# RobotBooster.net
KiCad netlist of a schematic drawn in EAGLE
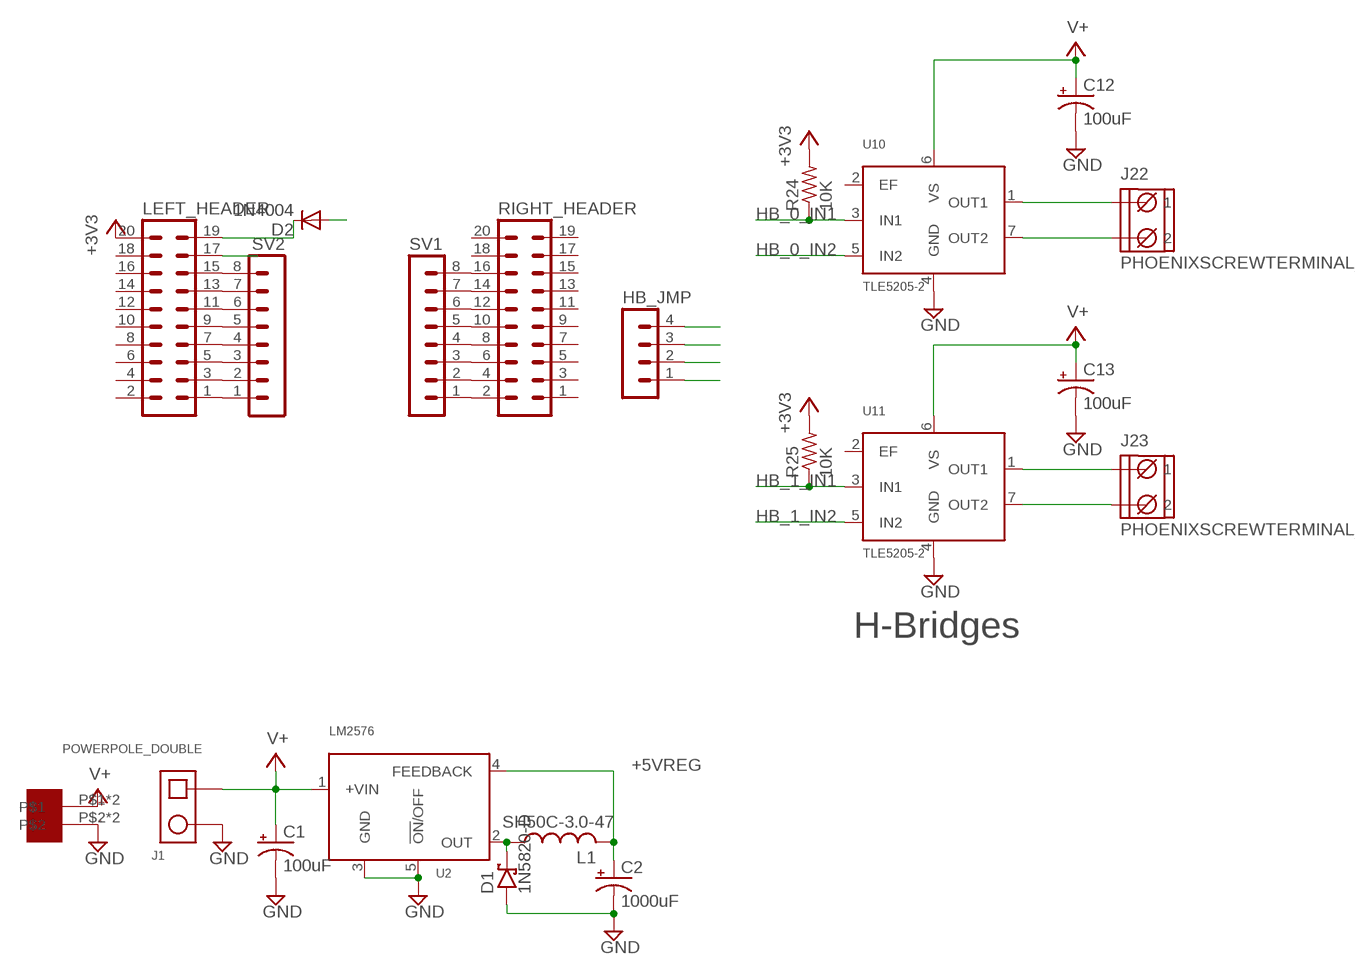
[diagram p0: schematic, sheet 1]

(export (version "E")
  (design (tool "Eeschema 10.0.6"))
  (components
    (comp (ref "C1")
      (value "100uF")
      (footprint "eagle-import:E3,5-8")
      (libsource (lib "eagle-import") (part "CPOL-USE3.5-8"))
    )
    (comp (ref "C2")
      (value "1000uF")
      (footprint "eagle-import:E5-10,5")
      (libsource (lib "eagle-import") (part "CPOL-USE5-10.5"))
    )
    (comp (ref "C12")
      (value "100uF")
      (footprint "eagle-import:E3,5-8")
      (libsource (lib "eagle-import") (part "CPOL-USE3.5-8"))
    )
    (comp (ref "C13")
      (value "100uF")
      (footprint "eagle-import:E3,5-8")
      (libsource (lib "eagle-import") (part "CPOL-USE3.5-8"))
    )
    (comp (ref "D1")
      (value "1N5820-D")
      (footprint "eagle-import:DIODE_17MM")
      (libsource (lib "eagle-import") (part "1N5820-D"))
    )
    (comp (ref "D2")
      (value "1N4004")
      (footprint "eagle-import:DO41-10")
      (libsource (lib "eagle-import") (part "1N4004"))
    )
    (comp (ref "HB_JMP")
      (value "MA04-1")
      (footprint "eagle-import:MA04-1")
      (libsource (lib "eagle-import") (part "MA04-1"))
    )
    (comp (ref "J1")
      (value "POWERPOLE_DOUBLE")
      (footprint "eagle-import:POWERPOLE_DOUBLE")
      (libsource (lib "eagle-import") (part "POWERPOLE_DOUBLE"))
    )
    (comp (ref "J22")
      (value "PHOENIXSCREWTERMINAL_2")
      (footprint "eagle-import:PHOENIXSCREWTERMINAL_2")
      (libsource (lib "eagle-import") (part "PHOENIXSCREWTERMINAL_2"))
    )
    (comp (ref "J23")
      (value "PHOENIXSCREWTERMINAL_2")
      (footprint "eagle-import:PHOENIXSCREWTERMINAL_2")
      (libsource (lib "eagle-import") (part "PHOENIXSCREWTERMINAL_2"))
    )
    (comp (ref "L1")
      (value "SH50C-3.0-47")
      (footprint "eagle-import:SH50-C2")
      (libsource (lib "eagle-import") (part "SH50C-3.0-47"))
    )
    (comp (ref "LEFT_HEADER")
      (value "MA10-2")
      (footprint "eagle-import:MA10-2")
      (libsource (lib "eagle-import") (part "MA10-2"))
    )
    (comp (ref "R24")
      (value "10K")
      (footprint "eagle-import:0204_5")
      (libsource (lib "eagle-import") (part "R-US_0204/5"))
    )
    (comp (ref "R25")
      (value "10K")
      (footprint "eagle-import:0204_5")
      (libsource (lib "eagle-import") (part "R-US_0204/5"))
    )
    (comp (ref "RIGHT_HEADER")
      (value "MA10-2")
      (footprint "eagle-import:MA10-2")
      (libsource (lib "eagle-import") (part "MA10-2"))
    )
    (comp (ref "SV1")
      (value "MA08-1")
      (footprint "eagle-import:MA08-1")
      (libsource (lib "eagle-import") (part "MA08-1"))
    )
    (comp (ref "SV2")
      (value "MA08-1")
      (footprint "eagle-import:MA08-1")
      (libsource (lib "eagle-import") (part "MA08-1"))
    )
    (comp (ref "U$1")
      (value ".200-2SMD")
      (footprint "eagle-import:HLE-108-02-X-DV-BE-A")
      (libsource (lib "eagle-import") (part ".200-2SMD"))
    )
    (comp (ref "U2")
      (value "LM2576")
      (footprint "eagle-import:TO-220-5")
      (libsource (lib "eagle-import") (part "LM2576"))
    )
    (comp (ref "U10")
      (value "TLE5205-2")
      (footprint "eagle-import:TO-220-7-11")
      (libsource (lib "eagle-import") (part "TLE5205-2"))
    )
    (comp (ref "U11")
      (value "TLE5205-2")
      (footprint "eagle-import:TO-220-7-11")
      (libsource (lib "eagle-import") (part "TLE5205-2"))
    )
  )
  (nets
    (net (code "1") (name "+3V3") (class "Default")
      (node (ref "LEFT_HEADER") (pin "20") (pinfunction "20_20") (pintype "passive"))
      (node (ref "R24") (pin "2") (pinfunction "2_2") (pintype "passive"))
      (node (ref "R25") (pin "2") (pinfunction "2_2") (pintype "passive"))
    )
    (net (code "2") (name "/+5VREG") (class "Default")
      (node (ref "C2") (pin "+") (pinfunction "+_+") (pintype "passive"))
      (node (ref "D2") (pin "A") (pinfunction "A_A") (pintype "passive"))
      (node (ref "L1") (pin "P$2") (pinfunction "2_P$2") (pintype "passive"))
      (node (ref "U2") (pin "4") (pinfunction "FEEDBACK_4") (pintype "bidirectional"))
    )
    (net (code "3") (name "/HB_0_IN1") (class "Default")
      (node (ref "HB_JMP") (pin "4") (pinfunction "4_4") (pintype "passive"))
      (node (ref "R24") (pin "1") (pinfunction "1_1") (pintype "passive"))
      (node (ref "U10") (pin "3") (pinfunction "IN1_3") (pintype "bidirectional"))
    )
    (net (code "4") (name "/HB_0_IN2") (class "Default")
      (node (ref "HB_JMP") (pin "3") (pinfunction "3_3") (pintype "passive"))
      (node (ref "U10") (pin "5") (pinfunction "IN2_5") (pintype "bidirectional"))
    )
    (net (code "5") (name "/HB_1_IN1") (class "Default")
      (node (ref "HB_JMP") (pin "2") (pinfunction "2_2") (pintype "passive"))
      (node (ref "R25") (pin "1") (pinfunction "1_1") (pintype "passive"))
      (node (ref "U11") (pin "3") (pinfunction "IN1_3") (pintype "bidirectional"))
    )
    (net (code "6") (name "/HB_1_IN2") (class "Default")
      (node (ref "HB_JMP") (pin "1") (pinfunction "1_1") (pintype "passive"))
      (node (ref "U11") (pin "5") (pinfunction "IN2_5") (pintype "bidirectional"))
    )
    (net (code "7") (name "GND") (class "Default")
      (node (ref "C1") (pin "-") (pinfunction "-_-") (pintype "passive"))
      (node (ref "C12") (pin "-") (pinfunction "-_-") (pintype "passive"))
      (node (ref "C13") (pin "-") (pinfunction "-_-") (pintype "passive"))
      (node (ref "C2") (pin "-") (pinfunction "-_-") (pintype "passive"))
      (node (ref "D1") (pin "2") (pinfunction "A_2") (pintype "passive"))
      (node (ref "J1") (pin "2") (pinfunction "2_2") (pintype "bidirectional"))
      (node (ref "LEFT_HEADER") (pin "17") (pinfunction "17_17") (pintype "passive"))
      (node (ref "U$1") (pin "P$2") (pinfunction "P$2_P$2") (pintype "bidirectional"))
      (node (ref "U$1") (pin "P$4") (pinfunction "P$2_P$4") (pintype "bidirectional"))
      (node (ref "U10") (pin "4") (pinfunction "GND_4") (pintype "bidirectional"))
      (node (ref "U11") (pin "4") (pinfunction "GND_4") (pintype "bidirectional"))
      (node (ref "U2") (pin "3") (pinfunction "GND_3") (pintype "bidirectional"))
      (node (ref "U2") (pin "5") (pinfunction "~{ON}/OFF_5") (pintype "bidirectional"))
    )
    (net (code "8") (name "Net-(D1-C)") (class "Default")
      (node (ref "D1") (pin "1") (pinfunction "C_1") (pintype "passive"))
      (node (ref "L1") (pin "P$1") (pinfunction "1_P$1") (pintype "passive"))
      (node (ref "U2") (pin "2") (pinfunction "OUT_2") (pintype "bidirectional"))
    )
    (net (code "9") (name "Net-(D2-PadC)") (class "Default")
      (node (ref "D2") (pin "C") (pinfunction "C_C") (pintype "passive"))
      (node (ref "LEFT_HEADER") (pin "19") (pinfunction "19_19") (pintype "passive"))
    )
    (net (code "10") (name "Net-(LEFT_HEADER-Pad1)") (class "Default")
      (node (ref "LEFT_HEADER") (pin "1") (pinfunction "1_1") (pintype "passive"))
      (node (ref "SV2") (pin "1") (pinfunction "1_1") (pintype "passive"))
    )
    (net (code "11") (name "Net-(LEFT_HEADER-Pad3)") (class "Default")
      (node (ref "LEFT_HEADER") (pin "3") (pinfunction "3_3") (pintype "passive"))
      (node (ref "SV2") (pin "2") (pinfunction "2_2") (pintype "passive"))
    )
    (net (code "12") (name "Net-(LEFT_HEADER-Pad5)") (class "Default")
      (node (ref "LEFT_HEADER") (pin "5") (pinfunction "5_5") (pintype "passive"))
      (node (ref "SV2") (pin "3") (pinfunction "3_3") (pintype "passive"))
    )
    (net (code "13") (name "Net-(LEFT_HEADER-Pad7)") (class "Default")
      (node (ref "LEFT_HEADER") (pin "7") (pinfunction "7_7") (pintype "passive"))
      (node (ref "SV2") (pin "4") (pinfunction "4_4") (pintype "passive"))
    )
    (net (code "14") (name "Net-(LEFT_HEADER-Pad9)") (class "Default")
      (node (ref "LEFT_HEADER") (pin "9") (pinfunction "9_9") (pintype "passive"))
      (node (ref "SV2") (pin "5") (pinfunction "5_5") (pintype "passive"))
    )
    (net (code "15") (name "Net-(LEFT_HEADER-Pad11)") (class "Default")
      (node (ref "LEFT_HEADER") (pin "11") (pinfunction "11_11") (pintype "passive"))
      (node (ref "SV2") (pin "6") (pinfunction "6_6") (pintype "passive"))
    )
    (net (code "16") (name "Net-(LEFT_HEADER-Pad13)") (class "Default")
      (node (ref "LEFT_HEADER") (pin "13") (pinfunction "13_13") (pintype "passive"))
      (node (ref "SV2") (pin "7") (pinfunction "7_7") (pintype "passive"))
    )
    (net (code "17") (name "Net-(LEFT_HEADER-Pad15)") (class "Default")
      (node (ref "LEFT_HEADER") (pin "15") (pinfunction "15_15") (pintype "passive"))
      (node (ref "SV2") (pin "8") (pinfunction "8_8") (pintype "passive"))
    )
    (net (code "18") (name "Net-(RIGHT_HEADER-Pad2)") (class "Default")
      (node (ref "RIGHT_HEADER") (pin "2") (pinfunction "2_2") (pintype "passive"))
      (node (ref "SV1") (pin "1") (pinfunction "1_1") (pintype "passive"))
    )
    (net (code "19") (name "Net-(RIGHT_HEADER-Pad4)") (class "Default")
      (node (ref "RIGHT_HEADER") (pin "4") (pinfunction "4_4") (pintype "passive"))
      (node (ref "SV1") (pin "2") (pinfunction "2_2") (pintype "passive"))
    )
    (net (code "20") (name "Net-(RIGHT_HEADER-Pad6)") (class "Default")
      (node (ref "RIGHT_HEADER") (pin "6") (pinfunction "6_6") (pintype "passive"))
      (node (ref "SV1") (pin "3") (pinfunction "3_3") (pintype "passive"))
    )
    (net (code "21") (name "Net-(RIGHT_HEADER-Pad8)") (class "Default")
      (node (ref "RIGHT_HEADER") (pin "8") (pinfunction "8_8") (pintype "passive"))
      (node (ref "SV1") (pin "4") (pinfunction "4_4") (pintype "passive"))
    )
    (net (code "22") (name "Net-(RIGHT_HEADER-Pad10)") (class "Default")
      (node (ref "RIGHT_HEADER") (pin "10") (pinfunction "10_10") (pintype "passive"))
      (node (ref "SV1") (pin "5") (pinfunction "5_5") (pintype "passive"))
    )
    (net (code "23") (name "Net-(RIGHT_HEADER-Pad12)") (class "Default")
      (node (ref "RIGHT_HEADER") (pin "12") (pinfunction "12_12") (pintype "passive"))
      (node (ref "SV1") (pin "6") (pinfunction "6_6") (pintype "passive"))
    )
    (net (code "24") (name "Net-(RIGHT_HEADER-Pad14)") (class "Default")
      (node (ref "RIGHT_HEADER") (pin "14") (pinfunction "14_14") (pintype "passive"))
      (node (ref "SV1") (pin "7") (pinfunction "7_7") (pintype "passive"))
    )
    (net (code "25") (name "Net-(RIGHT_HEADER-Pad16)") (class "Default")
      (node (ref "RIGHT_HEADER") (pin "16") (pinfunction "16_16") (pintype "passive"))
      (node (ref "SV1") (pin "8") (pinfunction "8_8") (pintype "passive"))
    )
    (net (code "26") (name "Net-(U10-OUT1)") (class "Default")
      (node (ref "J22") (pin "1") (pinfunction "1_1") (pintype "bidirectional"))
      (node (ref "U10") (pin "1") (pinfunction "OUT1_1") (pintype "bidirectional"))
    )
    (net (code "27") (name "Net-(U10-OUT2)") (class "Default")
      (node (ref "J22") (pin "2") (pinfunction "2_2") (pintype "bidirectional"))
      (node (ref "U10") (pin "7") (pinfunction "OUT2_7") (pintype "bidirectional"))
    )
    (net (code "28") (name "Net-(U11-OUT1)") (class "Default")
      (node (ref "J23") (pin "1") (pinfunction "1_1") (pintype "bidirectional"))
      (node (ref "U11") (pin "1") (pinfunction "OUT1_1") (pintype "bidirectional"))
    )
    (net (code "29") (name "Net-(U11-OUT2)") (class "Default")
      (node (ref "J23") (pin "2") (pinfunction "2_2") (pintype "bidirectional"))
      (node (ref "U11") (pin "7") (pinfunction "OUT2_7") (pintype "bidirectional"))
    )
    (net (code "30") (name "V+") (class "Default")
      (node (ref "C1") (pin "+") (pinfunction "+_+") (pintype "passive"))
      (node (ref "C12") (pin "+") (pinfunction "+_+") (pintype "passive"))
      (node (ref "C13") (pin "+") (pinfunction "+_+") (pintype "passive"))
      (node (ref "J1") (pin "1") (pinfunction "1_1") (pintype "bidirectional"))
      (node (ref "U$1") (pin "P$1") (pinfunction "P$1_P$1") (pintype "bidirectional"))
      (node (ref "U$1") (pin "P$3") (pinfunction "P$1_P$3") (pintype "bidirectional"))
      (node (ref "U10") (pin "6") (pinfunction "VS_6") (pintype "bidirectional"))
      (node (ref "U11") (pin "6") (pinfunction "VS_6") (pintype "bidirectional"))
      (node (ref "U2") (pin "1") (pinfunction "+VIN_1") (pintype "bidirectional"))
    )
    (net (code "31") (name "unconnected-(LEFT_HEADER-Pad2)") (class "Default")
      (node (ref "LEFT_HEADER") (pin "2") (pinfunction "2_2") (pintype "passive"))
    )
    (net (code "32") (name "unconnected-(LEFT_HEADER-Pad4)") (class "Default")
      (node (ref "LEFT_HEADER") (pin "4") (pinfunction "4_4") (pintype "passive"))
    )
    (net (code "33") (name "unconnected-(LEFT_HEADER-Pad6)") (class "Default")
      (node (ref "LEFT_HEADER") (pin "6") (pinfunction "6_6") (pintype "passive"))
    )
    (net (code "34") (name "unconnected-(LEFT_HEADER-Pad8)") (class "Default")
      (node (ref "LEFT_HEADER") (pin "8") (pinfunction "8_8") (pintype "passive"))
    )
    (net (code "35") (name "unconnected-(LEFT_HEADER-Pad10)") (class "Default")
      (node (ref "LEFT_HEADER") (pin "10") (pinfunction "10_10") (pintype "passive"))
    )
    (net (code "36") (name "unconnected-(LEFT_HEADER-Pad12)") (class "Default")
      (node (ref "LEFT_HEADER") (pin "12") (pinfunction "12_12") (pintype "passive"))
    )
    (net (code "37") (name "unconnected-(LEFT_HEADER-Pad14)") (class "Default")
      (node (ref "LEFT_HEADER") (pin "14") (pinfunction "14_14") (pintype "passive"))
    )
    (net (code "38") (name "unconnected-(LEFT_HEADER-Pad16)") (class "Default")
      (node (ref "LEFT_HEADER") (pin "16") (pinfunction "16_16") (pintype "passive"))
    )
    (net (code "39") (name "unconnected-(LEFT_HEADER-Pad18)") (class "Default")
      (node (ref "LEFT_HEADER") (pin "18") (pinfunction "18_18") (pintype "passive"))
    )
    (net (code "40") (name "unconnected-(RIGHT_HEADER-Pad1)") (class "Default")
      (node (ref "RIGHT_HEADER") (pin "1") (pinfunction "1_1") (pintype "passive"))
    )
    (net (code "41") (name "unconnected-(RIGHT_HEADER-Pad3)") (class "Default")
      (node (ref "RIGHT_HEADER") (pin "3") (pinfunction "3_3") (pintype "passive"))
    )
    (net (code "42") (name "unconnected-(RIGHT_HEADER-Pad5)") (class "Default")
      (node (ref "RIGHT_HEADER") (pin "5") (pinfunction "5_5") (pintype "passive"))
    )
    (net (code "43") (name "unconnected-(RIGHT_HEADER-Pad7)") (class "Default")
      (node (ref "RIGHT_HEADER") (pin "7") (pinfunction "7_7") (pintype "passive"))
    )
    (net (code "44") (name "unconnected-(RIGHT_HEADER-Pad9)") (class "Default")
      (node (ref "RIGHT_HEADER") (pin "9") (pinfunction "9_9") (pintype "passive"))
    )
    (net (code "45") (name "unconnected-(RIGHT_HEADER-Pad11)") (class "Default")
      (node (ref "RIGHT_HEADER") (pin "11") (pinfunction "11_11") (pintype "passive"))
    )
    (net (code "46") (name "unconnected-(RIGHT_HEADER-Pad13)") (class "Default")
      (node (ref "RIGHT_HEADER") (pin "13") (pinfunction "13_13") (pintype "passive"))
    )
    (net (code "47") (name "unconnected-(RIGHT_HEADER-Pad15)") (class "Default")
      (node (ref "RIGHT_HEADER") (pin "15") (pinfunction "15_15") (pintype "passive"))
    )
    (net (code "48") (name "unconnected-(RIGHT_HEADER-Pad17)") (class "Default")
      (node (ref "RIGHT_HEADER") (pin "17") (pinfunction "17_17") (pintype "passive"))
    )
    (net (code "49") (name "unconnected-(RIGHT_HEADER-Pad18)") (class "Default")
      (node (ref "RIGHT_HEADER") (pin "18") (pinfunction "18_18") (pintype "passive"))
    )
    (net (code "50") (name "unconnected-(RIGHT_HEADER-Pad19)") (class "Default")
      (node (ref "RIGHT_HEADER") (pin "19") (pinfunction "19_19") (pintype "passive"))
    )
    (net (code "51") (name "unconnected-(RIGHT_HEADER-Pad20)") (class "Default")
      (node (ref "RIGHT_HEADER") (pin "20") (pinfunction "20_20") (pintype "passive"))
    )
    (net (code "52") (name "unconnected-(U10-EF-Pad2)") (class "Default")
      (node (ref "U10") (pin "2") (pinfunction "EF_2") (pintype "bidirectional"))
    )
    (net (code "53") (name "unconnected-(U11-EF-Pad2)") (class "Default")
      (node (ref "U11") (pin "2") (pinfunction "EF_2") (pintype "bidirectional"))
    )
  )
)
